# BB3_Schematic.net
KiCad netlist of a schematic drawn in Altium Designer
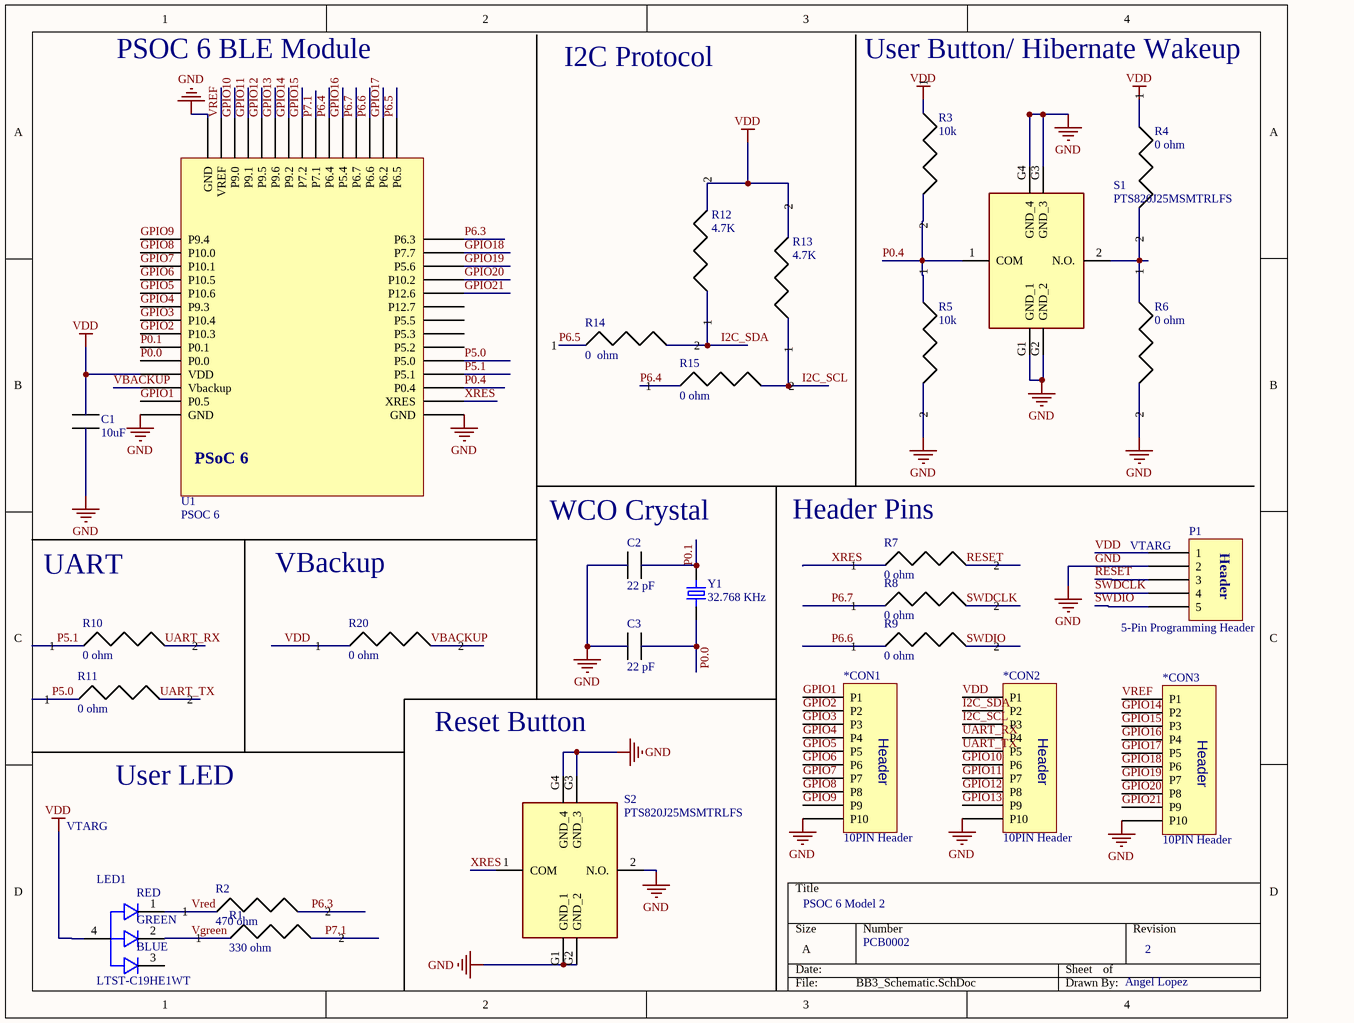
[diagram p0: BB3_Schematic.SchDoc]

(export (version "E")
  (design (tool "Eeschema 10.0.6"))
  (components
    (comp (ref "*CON1")
      (value "10PIN Header")
      (footprint "10 Pin Header")
      (libsource (lib "Lab1_library") (part "10PIN Header"))
    )
    (comp (ref "*CON2")
      (value "10PIN Header")
      (footprint "10 Pin Header")
      (libsource (lib "Lab1_library") (part "10PIN Header"))
    )
    (comp (ref "*CON3")
      (value "10PIN Header")
      (footprint "10 Pin Header")
      (libsource (lib "Lab1_library") (part "10PIN Header"))
    )
    (comp (ref "C1")
      (value "10uF")
      (footprint "Capacitor")
      (libsource (lib "Lab1_library") (part "Cap 0603"))
    )
    (comp (ref "C2")
      (value "22 pF")
      (footprint "Capacitor")
      (libsource (lib "Lab1_library") (part "Cap 0603"))
    )
    (comp (ref "C3")
      (value "22 pF")
      (footprint "Capacitor")
      (libsource (lib "Lab1_library") (part "Cap 0603"))
    )
    (comp (ref "LED1")
      (value "LTST-C19HE1WT")
      (footprint "LED_LTST-C19HE1WT")
      (fields (field (name "MF") "Lite-On Inc."))
      (libsource (lib "SeniorDesign") (part "LTST-C19HE1WT"))
    )
    (comp (ref "P1")
      (value "5-Pin Programming Header")
      (footprint "5pin Progamming Header")
      (libsource (lib "Lab1_library") (part "5-Pin Programming Header"))
    )
    (comp (ref "R1")
      (value "330 ohm")
      (footprint "Resistor")
      (libsource (lib "Lab1_library") (part "Resistor"))
    )
    (comp (ref "R2")
      (value "470 ohm")
      (footprint "Resistor")
      (libsource (lib "Lab1_library") (part "Resistor"))
    )
    (comp (ref "R3") (value "10k") (footprint "Resistor") (libsource (lib "Lab1_library") (part "Resistor")))
    (comp (ref "R4")
      (value "0 ohm")
      (footprint "Resistor")
      (libsource (lib "Lab1_library") (part "Resistor"))
    )
    (comp (ref "R5") (value "10k") (footprint "Resistor") (libsource (lib "Lab1_library") (part "Resistor")))
    (comp (ref "R6")
      (value "0 ohm")
      (footprint "Resistor")
      (libsource (lib "Lab1_library") (part "Resistor"))
    )
    (comp (ref "R7")
      (value "0 ohm")
      (footprint "Resistor")
      (libsource (lib "Lab1_library") (part "Resistor"))
    )
    (comp (ref "R8")
      (value "0 ohm")
      (footprint "Resistor")
      (libsource (lib "Lab1_library") (part "Resistor"))
    )
    (comp (ref "R9")
      (value "0 ohm")
      (footprint "Resistor")
      (libsource (lib "Lab1_library") (part "Resistor"))
    )
    (comp (ref "R10")
      (value "0 ohm")
      (footprint "Resistor")
      (libsource (lib "Lab1_library") (part "Resistor"))
    )
    (comp (ref "R11")
      (value "0 ohm")
      (footprint "Resistor")
      (libsource (lib "Lab1_library") (part "Resistor"))
    )
    (comp (ref "R12")
      (value "4.7K")
      (footprint "Resistor")
      (libsource (lib "Lab1_library") (part "Resistor"))
    )
    (comp (ref "R13")
      (value "4.7K")
      (footprint "Resistor")
      (libsource (lib "Lab1_library") (part "Resistor"))
    )
    (comp (ref "R14")
      (value "0  ohm")
      (footprint "Resistor")
      (libsource (lib "Lab1_library") (part "Resistor"))
    )
    (comp (ref "R15")
      (value "0 ohm")
      (footprint "Resistor")
      (libsource (lib "Lab1_library") (part "Resistor"))
    )
    (comp (ref "R20")
      (value "0 ohm")
      (footprint "Resistor")
      (libsource (lib "Lab1_library") (part "Resistor"))
    )
    (comp (ref "S1")
      (value "PTS820J25MSMTRLFS")
      (footprint "SamacSys:PTS820J25MSMTRLFS")
      (description "Switch")
      (fields (field (name "MOUSER PART NUMBER") "611-PTS820J25MSMTR"))
      (libsource (lib "*") (part "PTS820J25MSMTRLFS"))
    )
    (comp (ref "S2")
      (value "PTS820J25MSMTRLFS")
      (footprint "PTS820J25MSMTRLFS")
      (description "Switch")
      (fields (field (name "MOUSER PART NUMBER") "611-PTS820J25MSMTR"))
      (libsource (lib "SeniorDesign") (part "PTS820J25MSMTRLFS"))
    )
    (comp (ref "U1") (value "PSOC 6") (footprint "PSoC 6") (libsource (lib "Lab1_library") (part "PSOC 6")))
    (comp (ref "Y1")
      (value "32.768 KHz")
      (footprint "ECX-31B")
      (libsource (lib "Lab1_library") (part "ECX-31B"))
    )
  )
  (nets
    (net (code "1") (name "/GPIO1") (class "Default")
      (node (ref "*CON1") (pin "P1") (pinfunction "P1_P1") (pintype "passive"))
      (node (ref "U1") (pin "P0.5") (pinfunction "P0.5_P0.5") (pintype "passive"))
    )
    (net (code "2") (name "/GPIO2") (class "Default")
      (node (ref "*CON1") (pin "P2") (pinfunction "P2_P2") (pintype "passive"))
      (node (ref "U1") (pin "P10.3") (pinfunction "P10.3_P10.3") (pintype "passive"))
    )
    (net (code "3") (name "/GPIO3") (class "Default")
      (node (ref "*CON1") (pin "P3") (pinfunction "P3_P3") (pintype "passive"))
      (node (ref "U1") (pin "P10.4") (pinfunction "P10.4_P10.4") (pintype "passive"))
    )
    (net (code "4") (name "/GPIO4") (class "Default")
      (node (ref "*CON1") (pin "P4") (pinfunction "P4_P4") (pintype "passive"))
      (node (ref "U1") (pin "P9.3") (pinfunction "P9.3_P9.3") (pintype "passive"))
    )
    (net (code "5") (name "/GPIO5") (class "Default")
      (node (ref "*CON1") (pin "P5") (pinfunction "P5_P5") (pintype "passive"))
      (node (ref "U1") (pin "P10.6") (pinfunction "P10.6_P10.6") (pintype "passive"))
    )
    (net (code "6") (name "/GPIO6") (class "Default")
      (node (ref "*CON1") (pin "P6") (pinfunction "P6_P6") (pintype "passive"))
      (node (ref "U1") (pin "P10.5") (pinfunction "P10.5_P10.5") (pintype "passive"))
    )
    (net (code "7") (name "/GPIO7") (class "Default")
      (node (ref "*CON1") (pin "P7") (pinfunction "P7_P7") (pintype "passive"))
      (node (ref "U1") (pin "P10.1") (pinfunction "P10.1_P10.1") (pintype "passive"))
    )
    (net (code "8") (name "/GPIO8") (class "Default")
      (node (ref "*CON1") (pin "P8") (pinfunction "P8_P8") (pintype "passive"))
      (node (ref "U1") (pin "P10.0") (pinfunction "P10.0_P10.0") (pintype "passive"))
    )
    (net (code "9") (name "/GPIO9") (class "Default")
      (node (ref "*CON1") (pin "P9") (pinfunction "P9_P9") (pintype "passive"))
      (node (ref "U1") (pin "P9.4") (pinfunction "P9.4_P9.4") (pintype "passive"))
    )
    (net (code "10") (name "/GPIO10") (class "Default")
      (node (ref "*CON2") (pin "P6") (pinfunction "P6_P6") (pintype "passive"))
      (node (ref "U1") (pin "P9.0") (pinfunction "P9.0_P9.0") (pintype "passive"))
    )
    (net (code "11") (name "/GPIO11") (class "Default")
      (node (ref "*CON2") (pin "P7") (pinfunction "P7_P7") (pintype "passive"))
      (node (ref "U1") (pin "P9.1") (pinfunction "P9.1_P9.1") (pintype "passive"))
    )
    (net (code "12") (name "/GPIO12") (class "Default")
      (node (ref "*CON2") (pin "P8") (pinfunction "P8_P8") (pintype "passive"))
      (node (ref "U1") (pin "P9.5") (pinfunction "P9.5_P9.5") (pintype "passive"))
    )
    (net (code "13") (name "/GPIO13") (class "Default")
      (node (ref "*CON2") (pin "P9") (pinfunction "P9_P9") (pintype "passive"))
      (node (ref "U1") (pin "P9.6") (pinfunction "P9.6_P9.6") (pintype "passive"))
    )
    (net (code "14") (name "/GPIO14") (class "Default")
      (node (ref "*CON3") (pin "P2") (pinfunction "P2_P2") (pintype "passive"))
      (node (ref "U1") (pin "P9.2") (pinfunction "P9.2_P9.2") (pintype "passive"))
    )
    (net (code "15") (name "/GPIO15") (class "Default")
      (node (ref "*CON3") (pin "P3") (pinfunction "P3_P3") (pintype "passive"))
      (node (ref "U1") (pin "P7.2") (pinfunction "P7.2_P7.2") (pintype "passive"))
    )
    (net (code "16") (name "/GPIO16") (class "Default")
      (node (ref "*CON3") (pin "P4") (pinfunction "P4_P4") (pintype "passive"))
      (node (ref "U1") (pin "P5.4") (pinfunction "P5.4_P5.4") (pintype "passive"))
    )
    (net (code "17") (name "/GPIO17") (class "Default")
      (node (ref "*CON3") (pin "P5") (pinfunction "P5_P5") (pintype "passive"))
      (node (ref "U1") (pin "P6.2") (pinfunction "P6.2_P6.2") (pintype "passive"))
    )
    (net (code "18") (name "/GPIO18") (class "Default")
      (node (ref "*CON3") (pin "P6") (pinfunction "P6_P6") (pintype "passive"))
      (node (ref "U1") (pin "P7.7") (pinfunction "P7.7_P7.7") (pintype "passive"))
    )
    (net (code "19") (name "/GPIO19") (class "Default")
      (node (ref "*CON3") (pin "P7") (pinfunction "P7_P7") (pintype "passive"))
      (node (ref "U1") (pin "P5.6") (pinfunction "P5.6_P5.6") (pintype "passive"))
    )
    (net (code "20") (name "/GPIO20") (class "Default")
      (node (ref "*CON3") (pin "P8") (pinfunction "P8_P8") (pintype "passive"))
      (node (ref "U1") (pin "P10.2") (pinfunction "P10.2_P10.2") (pintype "passive"))
    )
    (net (code "21") (name "/GPIO21") (class "Default")
      (node (ref "*CON3") (pin "P9") (pinfunction "P9_P9") (pintype "passive"))
      (node (ref "U1") (pin "P12.6") (pinfunction "P12.6_P12.6") (pintype "passive"))
    )
    (net (code "22") (name "/I2C_SCL") (class "Default")
      (node (ref "*CON2") (pin "P3") (pinfunction "P3_P3") (pintype "passive"))
      (node (ref "R13") (pin "1") (pinfunction "1_1") (pintype "passive"))
      (node (ref "R15") (pin "2") (pinfunction "2_2") (pintype "passive"))
    )
    (net (code "23") (name "/I2C_SDA") (class "Default")
      (node (ref "*CON2") (pin "P2") (pinfunction "P2_P2") (pintype "passive"))
      (node (ref "R12") (pin "1") (pinfunction "1_1") (pintype "passive"))
      (node (ref "R14") (pin "2") (pinfunction "2_2") (pintype "passive"))
    )
    (net (code "24") (name "/P0.0") (class "Default")
      (node (ref "C3") (pin "2") (pinfunction "2_2") (pintype "passive"))
      (node (ref "U1") (pin "P0.0") (pinfunction "P0.0_P0.0") (pintype "passive"))
      (node (ref "Y1") (pin "1") (pinfunction "1_1") (pintype "passive"))
    )
    (net (code "25") (name "/P0.1") (class "Default")
      (node (ref "C2") (pin "2") (pinfunction "2_2") (pintype "passive"))
      (node (ref "U1") (pin "P0.1") (pinfunction "P0.1_P0.1") (pintype "passive"))
      (node (ref "Y1") (pin "2") (pinfunction "2_2") (pintype "passive"))
    )
    (net (code "26") (name "/P0.4") (class "Default")
      (node (ref "R3") (pin "2") (pinfunction "2_2") (pintype "passive"))
      (node (ref "R5") (pin "1") (pinfunction "1_1") (pintype "passive"))
      (node (ref "S1") (pin "1") (pinfunction "COM_1") (pintype "passive"))
      (node (ref "U1") (pin "P0.4") (pinfunction "P0.4_P0.4") (pintype "passive"))
    )
    (net (code "27") (name "/P5.0") (class "Default")
      (node (ref "R11") (pin "1") (pinfunction "1_1") (pintype "passive"))
      (node (ref "U1") (pin "P5.0") (pinfunction "P5.0_P5.0") (pintype "passive"))
    )
    (net (code "28") (name "/P5.1") (class "Default")
      (node (ref "R10") (pin "1") (pinfunction "1_1") (pintype "passive"))
      (node (ref "U1") (pin "P5.1") (pinfunction "P5.1_P5.1") (pintype "passive"))
    )
    (net (code "29") (name "/P6.3") (class "Default")
      (node (ref "R2") (pin "2") (pinfunction "2_2") (pintype "passive"))
      (node (ref "U1") (pin "P6.3") (pinfunction "P6.3_P6.3") (pintype "passive"))
    )
    (net (code "30") (name "/P6.4") (class "Default")
      (node (ref "R15") (pin "1") (pinfunction "1_1") (pintype "passive"))
      (node (ref "U1") (pin "P6.4") (pinfunction "P6.4_P6.4") (pintype "passive"))
    )
    (net (code "31") (name "/P6.5") (class "Default")
      (node (ref "R14") (pin "1") (pinfunction "1_1") (pintype "passive"))
      (node (ref "U1") (pin "P6.5") (pinfunction "P6.5_P6.5") (pintype "passive"))
    )
    (net (code "32") (name "/P6.6") (class "Default")
      (node (ref "R9") (pin "1") (pinfunction "1_1") (pintype "passive"))
      (node (ref "U1") (pin "P6.6") (pinfunction "P6.6_P6.6") (pintype "passive"))
    )
    (net (code "33") (name "/P6.7") (class "Default")
      (node (ref "R8") (pin "1") (pinfunction "1_1") (pintype "passive"))
      (node (ref "U1") (pin "P6.7") (pinfunction "P6.7_P6.7") (pintype "passive"))
    )
    (net (code "34") (name "/P7.1") (class "Default")
      (node (ref "R1") (pin "2") (pinfunction "2_2") (pintype "passive"))
      (node (ref "U1") (pin "P7.1") (pinfunction "P7.1_P7.1") (pintype "passive"))
    )
    (net (code "35") (name "/RESET") (class "Default")
      (node (ref "P1") (pin "3") (pinfunction "3_3") (pintype "passive"))
      (node (ref "R7") (pin "2") (pinfunction "2_2") (pintype "passive"))
    )
    (net (code "36") (name "/SWDCLK") (class "Default")
      (node (ref "P1") (pin "4") (pinfunction "4_4") (pintype "passive"))
      (node (ref "R8") (pin "2") (pinfunction "2_2") (pintype "passive"))
    )
    (net (code "37") (name "/SWDIO") (class "Default")
      (node (ref "P1") (pin "5") (pinfunction "5_5") (pintype "passive"))
      (node (ref "R9") (pin "2") (pinfunction "2_2") (pintype "passive"))
    )
    (net (code "38") (name "/UART_RX") (class "Default")
      (node (ref "*CON2") (pin "P4") (pinfunction "P4_P4") (pintype "passive"))
      (node (ref "R10") (pin "2") (pinfunction "2_2") (pintype "passive"))
    )
    (net (code "39") (name "/UART_TX") (class "Default")
      (node (ref "*CON2") (pin "P5") (pinfunction "P5_P5") (pintype "passive"))
      (node (ref "R11") (pin "2") (pinfunction "2_2") (pintype "passive"))
    )
    (net (code "40") (name "/VBACKUP") (class "Default")
      (node (ref "R20") (pin "2") (pinfunction "2_2") (pintype "passive"))
      (node (ref "U1") (pin "Vbackup") (pinfunction "Vbackup_Vbackup") (pintype "passive"))
    )
    (net (code "41") (name "/VREF") (class "Default")
      (node (ref "*CON3") (pin "P1") (pinfunction "P1_P1") (pintype "passive"))
      (node (ref "U1") (pin "VREF") (pinfunction "VREF_VREF") (pintype "passive"))
    )
    (net (code "42") (name "/Vgreen") (class "Default")
      (node (ref "LED1") (pin "2") (pinfunction "2_2") (pintype "passive"))
      (node (ref "R1") (pin "1") (pinfunction "1_1") (pintype "passive"))
    )
    (net (code "43") (name "/Vred") (class "Default")
      (node (ref "LED1") (pin "1") (pinfunction "1_1") (pintype "passive"))
      (node (ref "R2") (pin "1") (pinfunction "1_1") (pintype "passive"))
    )
    (net (code "44") (name "/XRES") (class "Default")
      (node (ref "R7") (pin "1") (pinfunction "1_1") (pintype "passive"))
      (node (ref "S2") (pin "1") (pinfunction "COM_1") (pintype "passive"))
      (node (ref "U1") (pin "XRES") (pinfunction "XRES_XRES") (pintype "passive"))
    )
    (net (code "45") (name "GND") (class "Default")
      (node (ref "*CON1") (pin "P10") (pinfunction "P10_P10") (pintype "passive"))
      (node (ref "*CON2") (pin "P10") (pinfunction "P10_P10") (pintype "passive"))
      (node (ref "*CON3") (pin "P10") (pinfunction "P10_P10") (pintype "passive"))
      (node (ref "C1") (pin "2") (pinfunction "2_2") (pintype "passive"))
      (node (ref "C2") (pin "1") (pinfunction "1_1") (pintype "passive"))
      (node (ref "C3") (pin "1") (pinfunction "1_1") (pintype "passive"))
      (node (ref "P1") (pin "2") (pinfunction "2_2") (pintype "passive"))
      (node (ref "R5") (pin "2") (pinfunction "2_2") (pintype "passive"))
      (node (ref "R6") (pin "2") (pinfunction "2_2") (pintype "passive"))
      (node (ref "S1") (pin "G1") (pinfunction "GND_1_G1") (pintype "passive"))
      (node (ref "S1") (pin "G2") (pinfunction "GND_2_G2") (pintype "passive"))
      (node (ref "S1") (pin "G3") (pinfunction "GND_3_G3") (pintype "passive"))
      (node (ref "S1") (pin "G4") (pinfunction "GND_4_G4") (pintype "passive"))
      (node (ref "S2") (pin "2") (pinfunction "N.O._2") (pintype "passive"))
      (node (ref "S2") (pin "G1") (pinfunction "GND_1_G1") (pintype "passive"))
      (node (ref "S2") (pin "G2") (pinfunction "GND_2_G2") (pintype "passive"))
      (node (ref "S2") (pin "G3") (pinfunction "GND_3_G3") (pintype "passive"))
      (node (ref "S2") (pin "G4") (pinfunction "GND_4_G4") (pintype "passive"))
      (node (ref "U1") (pin "GND") (pinfunction "GND_GND") (pintype "passive"))
    )
    (net (code "46") (name "Net-(S1-N.O.)") (class "Default")
      (node (ref "R4") (pin "2") (pinfunction "2_2") (pintype "passive"))
      (node (ref "R6") (pin "1") (pinfunction "1_1") (pintype "passive"))
      (node (ref "S1") (pin "2") (pinfunction "N.O._2") (pintype "passive"))
    )
    (net (code "47") (name "VDD") (class "Default")
      (node (ref "*CON2") (pin "P1") (pinfunction "P1_P1") (pintype "passive"))
      (node (ref "C1") (pin "1") (pinfunction "1_1") (pintype "passive"))
      (node (ref "LED1") (pin "4") (pinfunction "4_4") (pintype "passive"))
      (node (ref "P1") (pin "1") (pinfunction "1_1") (pintype "passive"))
      (node (ref "R12") (pin "2") (pinfunction "2_2") (pintype "passive"))
      (node (ref "R13") (pin "2") (pinfunction "2_2") (pintype "passive"))
      (node (ref "R20") (pin "1") (pinfunction "1_1") (pintype "passive"))
      (node (ref "R3") (pin "1") (pinfunction "1_1") (pintype "passive"))
      (node (ref "R4") (pin "1") (pinfunction "1_1") (pintype "passive"))
      (node (ref "U1") (pin "VDD") (pinfunction "VDD_VDD") (pintype "passive"))
    )
    (net (code "48") (name "unconnected-(LED1-Pad3)") (class "Default")
      (node (ref "LED1") (pin "3") (pinfunction "3_3") (pintype "passive"))
    )
    (net (code "49") (name "unconnected-(U1-PadP5.2)") (class "Default")
      (node (ref "U1") (pin "P5.2") (pinfunction "P5.2_P5.2") (pintype "passive"))
    )
    (net (code "50") (name "unconnected-(U1-PadP5.3)") (class "Default")
      (node (ref "U1") (pin "P5.3") (pinfunction "P5.3_P5.3") (pintype "passive"))
    )
    (net (code "51") (name "unconnected-(U1-PadP5.5)") (class "Default")
      (node (ref "U1") (pin "P5.5") (pinfunction "P5.5_P5.5") (pintype "passive"))
    )
    (net (code "52") (name "unconnected-(U1-PadP12.7)") (class "Default")
      (node (ref "U1") (pin "P12.7") (pinfunction "P12.7_P12.7") (pintype "passive"))
    )
  )
)
